# X_Axis_Stepper_Motor_Driver.net
KiCad netlist of a schematic drawn in Altium Designer
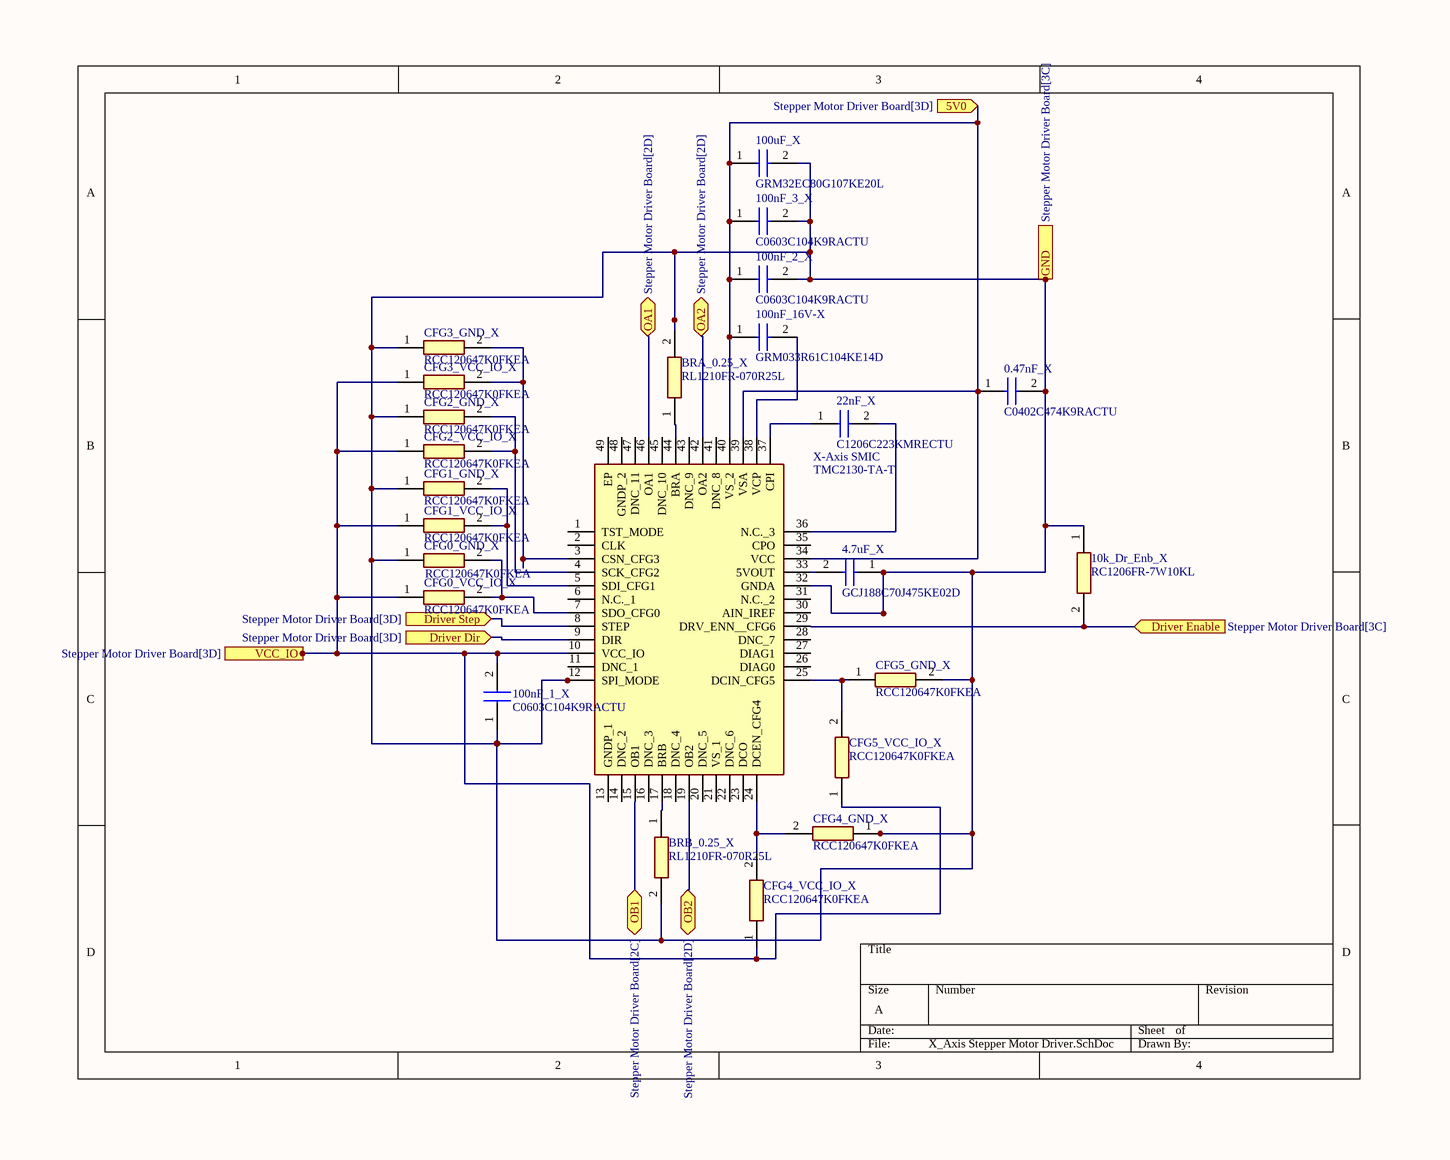
[diagram p0: X_Axis Stepper Motor Driver.SchDoc]

(export (version "E")
  (design (tool "Eeschema 10.0.6"))
  (components
    (comp (ref "0.47nF_X")
      (value "C0402C474K9RACTU")
      (footprint "SamacSys:CAPC1005X55N")
      (description "Capacitor")
      (fields (field (name "MOUSER PART NUMBER") "80-C0402C474K9RACTU"))
      (libsource (lib "*") (part "C0402C474K9RACTU"))
    )
    (comp (ref "4.7uF_X")
      (value "GCJ188C70J475KE02D")
      (footprint "SamacSys:CAPC1608X100N")
      (description "Capacitor")
      (fields (field (name "MOUSER PART NUMBER") "81-GCJ188C70J475KE2D"))
      (libsource (lib "*") (part "GCJ188C70J475KE02D"))
    )
    (comp (ref "10k_Dr_Enb_X")
      (value "RC1206FR-7W10KL")
      (footprint "SamacSys:RESC3116X65N")
      (description "Resistor")
      (libsource (lib "*") (part "RC1206FR-7W10KL"))
    )
    (comp (ref "22nF_X")
      (value "C1206C223KMRECTU")
      (footprint "SamacSys:C1206")
      (description "Capacitor")
      (fields (field (name "MOUSER PART NUMBER") "80-C1206C223KMRECTU"))
      (libsource (lib "*") (part "C1206C223KMRECTU"))
    )
    (comp (ref "100nF_1_X")
      (value "C0603C104K9RACTU")
      (footprint "SamacSys:C0603")
      (description "Capacitor")
      (fields (field (name "MOUSER PART NUMBER") "80-C0603C104K9R"))
      (libsource (lib "*") (part "C0603C104K9RACTU"))
    )
    (comp (ref "100nF_2_X")
      (value "C0603C104K9RACTU")
      (footprint "SamacSys:C0603")
      (description "Capacitor")
      (fields (field (name "MOUSER PART NUMBER") "80-C0603C104K9R"))
      (libsource (lib "*") (part "C0603C104K9RACTU"))
    )
    (comp (ref "100nF_3_X")
      (value "C0603C104K9RACTU")
      (footprint "SamacSys:C0603")
      (description "Capacitor")
      (fields (field (name "MOUSER PART NUMBER") "80-C0603C104K9R"))
      (libsource (lib "*") (part "C0603C104K9RACTU"))
    )
    (comp (ref "100nF_16V-X")
      (value "GRM033R61C104KE14D")
      (footprint "SamacSys:CAPC0603X33N")
      (description "Capacitor")
      (fields (field (name "MOUSER PART NUMBER") "81-GRM033R61C104KE4D"))
      (libsource (lib "*") (part "GRM033R61C104KE14D"))
    )
    (comp (ref "100uF_X")
      (value "GRM32EC80G107KE20L")
      (footprint "SamacSys:CAPC3225X270N")
      (description "Capacitor")
      (fields (field (name "MOUSER PART NUMBER") "81-GRM32EC80G107KE0L"))
      (libsource (lib "*") (part "GRM32EC80G107KE20L"))
    )
    (comp (ref "BRA_0.25_X")
      (value "RL1210FR-070R25L")
      (footprint "SamacSys:RESC3126X65N")
      (description "Resistor")
      (fields (field (name "MOUSER PART NUMBER") "603-RL1210FR-070R25L"))
      (libsource (lib "") (part "RL1210FR-070R25L_1"))
    )
    (comp (ref "BRB_0.25_X")
      (value "RL1210FR-070R25L")
      (footprint "SamacSys:RESC3126X65N")
      (description "Resistor")
      (fields (field (name "MOUSER PART NUMBER") "603-RL1210FR-070R25L"))
      (libsource (lib "*") (part "RL1210FR-070R25L"))
    )
    (comp (ref "CFG0_GND_X")
      (value "RCC120647K0FKEA")
      (footprint "SamacSys:RCC1206_e3")
      (description "Resistor")
      (fields (field (name "MOUSER PART NUMBER") "71-RCC120647K0FKEA"))
      (libsource (lib "") (part "RCC120647K0FKEA_1"))
    )
    (comp (ref "CFG0_VCC_IO_X")
      (value "RCC120647K0FKEA")
      (footprint "SamacSys:RCC1206_e3")
      (description "Resistor")
      (fields (field (name "MOUSER PART NUMBER") "71-RCC120647K0FKEA"))
      (libsource (lib "") (part "RCC120647K0FKEA_1"))
    )
    (comp (ref "CFG1_GND_X")
      (value "RCC120647K0FKEA")
      (footprint "SamacSys:RCC1206_e3")
      (description "Resistor")
      (fields (field (name "MOUSER PART NUMBER") "71-RCC120647K0FKEA"))
      (libsource (lib "") (part "RCC120647K0FKEA_1"))
    )
    (comp (ref "CFG1_VCC_IO_X")
      (value "RCC120647K0FKEA")
      (footprint "SamacSys:RCC1206_e3")
      (description "Resistor")
      (fields (field (name "MOUSER PART NUMBER") "71-RCC120647K0FKEA"))
      (libsource (lib "") (part "RCC120647K0FKEA_1"))
    )
    (comp (ref "CFG2_GND_X")
      (value "RCC120647K0FKEA")
      (footprint "SamacSys:RCC1206_e3")
      (description "Resistor")
      (fields (field (name "MOUSER PART NUMBER") "71-RCC120647K0FKEA"))
      (libsource (lib "") (part "RCC120647K0FKEA_1"))
    )
    (comp (ref "CFG2_VCC_IO_X")
      (value "RCC120647K0FKEA")
      (footprint "SamacSys:RCC1206_e3")
      (description "Resistor")
      (fields (field (name "MOUSER PART NUMBER") "71-RCC120647K0FKEA"))
      (libsource (lib "") (part "RCC120647K0FKEA_1"))
    )
    (comp (ref "CFG3_GND_X")
      (value "RCC120647K0FKEA")
      (footprint "SamacSys:RCC1206_e3")
      (description "Resistor")
      (fields (field (name "MOUSER PART NUMBER") "71-RCC120647K0FKEA"))
      (libsource (lib "") (part "RCC120647K0FKEA_1"))
    )
    (comp (ref "CFG3_VCC_IO_X")
      (value "RCC120647K0FKEA")
      (footprint "SamacSys:RCC1206_e3")
      (description "Resistor")
      (fields (field (name "MOUSER PART NUMBER") "71-RCC120647K0FKEA"))
      (libsource (lib "") (part "RCC120647K0FKEA_1"))
    )
    (comp (ref "CFG4_GND_X")
      (value "RCC120647K0FKEA")
      (footprint "SamacSys:RCC1206_e3")
      (description "Resistor")
      (fields (field (name "MOUSER PART NUMBER") "71-RCC120647K0FKEA"))
      (libsource (lib "") (part "RCC120647K0FKEA_2"))
    )
    (comp (ref "CFG4_VCC_IO_X")
      (value "RCC120647K0FKEA")
      (footprint "SamacSys:RCC1206_e3")
      (description "Resistor")
      (fields (field (name "MOUSER PART NUMBER") "71-RCC120647K0FKEA"))
      (libsource (lib "*") (part "RCC120647K0FKEA"))
    )
    (comp (ref "CFG5_GND_X")
      (value "RCC120647K0FKEA")
      (footprint "SamacSys:RCC1206_e3")
      (description "Resistor")
      (fields (field (name "MOUSER PART NUMBER") "71-RCC120647K0FKEA"))
      (libsource (lib "") (part "RCC120647K0FKEA_1"))
    )
    (comp (ref "CFG5_VCC_IO_X")
      (value "RCC120647K0FKEA")
      (footprint "SamacSys:RCC1206_e3")
      (description "Resistor")
      (fields (field (name "MOUSER PART NUMBER") "71-RCC120647K0FKEA"))
      (libsource (lib "*") (part "RCC120647K0FKEA"))
    )
    (comp (ref "X-Axis SMIC")
      (value "TMC2130-TA-T")
      (footprint "SamacSys:QFP50P900X900X120-49N")
      (description "Integrated Circuit")
      (fields (field (name "MOUSER PART NUMBER") "700-TMC2130-TA-T"))
      (libsource (lib "*") (part "TMC2130-TA-T"))
    )
  )
  (nets
    (net (code "1") (name "/5V0") (class "Default")
      (node (ref "0.47nF_X") (pin "1") (pinfunction "1_1") (pintype "passive"))
      (node (ref "100nF_16V-X") (pin "1") (pinfunction "1_1") (pintype "passive"))
      (node (ref "100nF_2_X") (pin "1") (pinfunction "1_1") (pintype "passive"))
      (node (ref "100nF_3_X") (pin "1") (pinfunction "1_1") (pintype "passive"))
      (node (ref "100uF_X") (pin "1") (pinfunction "1_1") (pintype "passive"))
      (node (ref "X-Axis SMIC") (pin "34") (pinfunction "VCC_34") (pintype "passive"))
      (node (ref "X-Axis SMIC") (pin "39") (pinfunction "VSA_39") (pintype "passive"))
      (node (ref "X-Axis SMIC") (pin "40") (pinfunction "VS_2_40") (pintype "passive"))
    )
    (net (code "2") (name "/Driver Dir") (class "Default")
      (node (ref "X-Axis SMIC") (pin "9") (pinfunction "DIR_9") (pintype "passive"))
    )
    (net (code "3") (name "/Driver Enable") (class "Default")
      (node (ref "10k_Dr_Enb_X") (pin "2") (pinfunction "2_2") (pintype "passive"))
      (node (ref "X-Axis SMIC") (pin "29") (pinfunction "DRV_ENN__CFG6_29") (pintype "passive"))
    )
    (net (code "4") (name "/Driver Step") (class "Default")
      (node (ref "X-Axis SMIC") (pin "8") (pinfunction "STEP_8") (pintype "passive"))
    )
    (net (code "5") (name "/GND") (class "Default")
      (node (ref "0.47nF_X") (pin "2") (pinfunction "2_2") (pintype "passive"))
      (node (ref "100nF_1_X") (pin "1") (pinfunction "1_1") (pintype "passive"))
      (node (ref "100nF_2_X") (pin "2") (pinfunction "2_2") (pintype "passive"))
      (node (ref "100nF_3_X") (pin "2") (pinfunction "2_2") (pintype "passive"))
      (node (ref "100uF_X") (pin "2") (pinfunction "2_2") (pintype "passive"))
      (node (ref "10k_Dr_Enb_X") (pin "1") (pinfunction "1_1") (pintype "passive"))
      (node (ref "4.7uF_X") (pin "1") (pinfunction "1_1") (pintype "passive"))
      (node (ref "BRA_0.25_X") (pin "2") (pinfunction "2_2") (pintype "passive"))
      (node (ref "BRB_0.25_X") (pin "2") (pinfunction "2_2") (pintype "passive"))
      (node (ref "CFG0_GND_X") (pin "1") (pinfunction "1_1") (pintype "passive"))
      (node (ref "CFG1_GND_X") (pin "1") (pinfunction "1_1") (pintype "passive"))
      (node (ref "CFG2_GND_X") (pin "1") (pinfunction "1_1") (pintype "passive"))
      (node (ref "CFG3_GND_X") (pin "1") (pinfunction "1_1") (pintype "passive"))
      (node (ref "CFG4_GND_X") (pin "1") (pinfunction "1_1") (pintype "passive"))
      (node (ref "CFG5_GND_X") (pin "2") (pinfunction "2_2") (pintype "passive"))
      (node (ref "X-Axis SMIC") (pin "12") (pinfunction "SPI_MODE_12") (pintype "passive"))
      (node (ref "X-Axis SMIC") (pin "32") (pinfunction "GNDA_32") (pintype "passive"))
    )
    (net (code "6") (name "/OA1") (class "Default")
      (node (ref "X-Axis SMIC") (pin "46") (pinfunction "OA1_46") (pintype "passive"))
    )
    (net (code "7") (name "/OA2") (class "Default")
      (node (ref "X-Axis SMIC") (pin "42") (pinfunction "OA2_42") (pintype "passive"))
    )
    (net (code "8") (name "/OB1") (class "Default")
      (node (ref "X-Axis SMIC") (pin "15") (pinfunction "OB1_15") (pintype "passive"))
    )
    (net (code "9") (name "/OB2") (class "Default")
      (node (ref "X-Axis SMIC") (pin "19") (pinfunction "OB2_19") (pintype "passive"))
    )
    (net (code "10") (name "/VCC_IO") (class "Default")
      (node (ref "100nF_1_X") (pin "2") (pinfunction "2_2") (pintype "passive"))
      (node (ref "CFG0_VCC_IO_X") (pin "1") (pinfunction "1_1") (pintype "passive"))
      (node (ref "CFG1_VCC_IO_X") (pin "1") (pinfunction "1_1") (pintype "passive"))
      (node (ref "CFG2_VCC_IO_X") (pin "1") (pinfunction "1_1") (pintype "passive"))
      (node (ref "CFG3_VCC_IO_X") (pin "1") (pinfunction "1_1") (pintype "passive"))
      (node (ref "CFG4_VCC_IO_X") (pin "1") (pinfunction "1_1") (pintype "passive"))
      (node (ref "CFG5_VCC_IO_X") (pin "1") (pinfunction "1_1") (pintype "passive"))
      (node (ref "X-Axis SMIC") (pin "10") (pinfunction "VCC_IO_10") (pintype "passive"))
    )
    (net (code "11") (name "Net-(X-Axis SMIC-5VOUT)") (class "Default")
      (node (ref "4.7uF_X") (pin "2") (pinfunction "2_2") (pintype "passive"))
      (node (ref "X-Axis SMIC") (pin "33") (pinfunction "5VOUT_33") (pintype "passive"))
    )
    (net (code "12") (name "Net-(X-Axis SMIC-BRA)") (class "Default")
      (node (ref "BRA_0.25_X") (pin "1") (pinfunction "1_1") (pintype "passive"))
      (node (ref "X-Axis SMIC") (pin "44") (pinfunction "BRA_44") (pintype "passive"))
    )
    (net (code "13") (name "Net-(X-Axis SMIC-BRB)") (class "Default")
      (node (ref "BRB_0.25_X") (pin "1") (pinfunction "1_1") (pintype "passive"))
      (node (ref "X-Axis SMIC") (pin "17") (pinfunction "BRB_17") (pintype "passive"))
    )
    (net (code "14") (name "Net-(X-Axis SMIC-CPI)") (class "Default")
      (node (ref "22nF_X") (pin "1") (pinfunction "1_1") (pintype "passive"))
      (node (ref "X-Axis SMIC") (pin "37") (pinfunction "CPI_37") (pintype "passive"))
    )
    (net (code "15") (name "Net-(X-Axis SMIC-CSN_CFG3)") (class "Default")
      (node (ref "CFG3_GND_X") (pin "2") (pinfunction "2_2") (pintype "passive"))
      (node (ref "CFG3_VCC_IO_X") (pin "2") (pinfunction "2_2") (pintype "passive"))
      (node (ref "X-Axis SMIC") (pin "3") (pinfunction "CSN_CFG3_3") (pintype "passive"))
    )
    (net (code "16") (name "Net-(X-Axis SMIC-DCEN_CFG4)") (class "Default")
      (node (ref "CFG4_GND_X") (pin "2") (pinfunction "2_2") (pintype "passive"))
      (node (ref "CFG4_VCC_IO_X") (pin "2") (pinfunction "2_2") (pintype "passive"))
      (node (ref "X-Axis SMIC") (pin "24") (pinfunction "DCEN_CFG4_24") (pintype "passive"))
    )
    (net (code "17") (name "Net-(X-Axis SMIC-DCIN_CFG5)") (class "Default")
      (node (ref "CFG5_GND_X") (pin "1") (pinfunction "1_1") (pintype "passive"))
      (node (ref "CFG5_VCC_IO_X") (pin "2") (pinfunction "2_2") (pintype "passive"))
      (node (ref "X-Axis SMIC") (pin "25") (pinfunction "DCIN_CFG5_25") (pintype "passive"))
    )
    (net (code "18") (name "Net-(X-Axis SMIC-N.C._3)") (class "Default")
      (node (ref "22nF_X") (pin "2") (pinfunction "2_2") (pintype "passive"))
      (node (ref "X-Axis SMIC") (pin "36") (pinfunction "N.C._3_36") (pintype "passive"))
    )
    (net (code "19") (name "Net-(X-Axis SMIC-SCK_CFG2)") (class "Default")
      (node (ref "CFG2_GND_X") (pin "2") (pinfunction "2_2") (pintype "passive"))
      (node (ref "CFG2_VCC_IO_X") (pin "2") (pinfunction "2_2") (pintype "passive"))
      (node (ref "X-Axis SMIC") (pin "4") (pinfunction "SCK_CFG2_4") (pintype "passive"))
    )
    (net (code "20") (name "Net-(X-Axis SMIC-SDI_CFG1)") (class "Default")
      (node (ref "CFG1_GND_X") (pin "2") (pinfunction "2_2") (pintype "passive"))
      (node (ref "CFG1_VCC_IO_X") (pin "2") (pinfunction "2_2") (pintype "passive"))
      (node (ref "X-Axis SMIC") (pin "5") (pinfunction "SDI_CFG1_5") (pintype "passive"))
    )
    (net (code "21") (name "Net-(X-Axis SMIC-SDO_CFG0)") (class "Default")
      (node (ref "CFG0_GND_X") (pin "2") (pinfunction "2_2") (pintype "passive"))
      (node (ref "CFG0_VCC_IO_X") (pin "2") (pinfunction "2_2") (pintype "passive"))
      (node (ref "X-Axis SMIC") (pin "7") (pinfunction "SDO_CFG0_7") (pintype "passive"))
    )
    (net (code "22") (name "Net-(X-Axis SMIC-VCP)") (class "Default")
      (node (ref "100nF_16V-X") (pin "2") (pinfunction "2_2") (pintype "passive"))
      (node (ref "X-Axis SMIC") (pin "38") (pinfunction "VCP_38") (pintype "passive"))
    )
    (net (code "23") (name "unconnected-(X-Axis SMIC-AIN_IREF-Pad30)") (class "Default")
      (node (ref "X-Axis SMIC") (pin "30") (pinfunction "AIN_IREF_30") (pintype "passive"))
    )
    (net (code "24") (name "unconnected-(X-Axis SMIC-CLK-Pad2)") (class "Default")
      (node (ref "X-Axis SMIC") (pin "2") (pinfunction "CLK_2") (pintype "passive"))
    )
    (net (code "25") (name "unconnected-(X-Axis SMIC-CPO-Pad35)") (class "Default")
      (node (ref "X-Axis SMIC") (pin "35") (pinfunction "CPO_35") (pintype "passive"))
    )
    (net (code "26") (name "unconnected-(X-Axis SMIC-DCO-Pad23)") (class "Default")
      (node (ref "X-Axis SMIC") (pin "23") (pinfunction "DCO_23") (pintype "passive"))
    )
    (net (code "27") (name "unconnected-(X-Axis SMIC-DIAG0-Pad26)") (class "Default")
      (node (ref "X-Axis SMIC") (pin "26") (pinfunction "DIAG0_26") (pintype "passive"))
    )
    (net (code "28") (name "unconnected-(X-Axis SMIC-DIAG1-Pad27)") (class "Default")
      (node (ref "X-Axis SMIC") (pin "27") (pinfunction "DIAG1_27") (pintype "passive"))
    )
    (net (code "29") (name "unconnected-(X-Axis SMIC-DNC_1-Pad11)") (class "Default")
      (node (ref "X-Axis SMIC") (pin "11") (pinfunction "DNC_1_11") (pintype "passive"))
    )
    (net (code "30") (name "unconnected-(X-Axis SMIC-DNC_2-Pad14)") (class "Default")
      (node (ref "X-Axis SMIC") (pin "14") (pinfunction "DNC_2_14") (pintype "passive"))
    )
    (net (code "31") (name "unconnected-(X-Axis SMIC-DNC_3-Pad16)") (class "Default")
      (node (ref "X-Axis SMIC") (pin "16") (pinfunction "DNC_3_16") (pintype "passive"))
    )
    (net (code "32") (name "unconnected-(X-Axis SMIC-DNC_4-Pad18)") (class "Default")
      (node (ref "X-Axis SMIC") (pin "18") (pinfunction "DNC_4_18") (pintype "passive"))
    )
    (net (code "33") (name "unconnected-(X-Axis SMIC-DNC_5-Pad20)") (class "Default")
      (node (ref "X-Axis SMIC") (pin "20") (pinfunction "DNC_5_20") (pintype "passive"))
    )
    (net (code "34") (name "unconnected-(X-Axis SMIC-DNC_6-Pad22)") (class "Default")
      (node (ref "X-Axis SMIC") (pin "22") (pinfunction "DNC_6_22") (pintype "passive"))
    )
    (net (code "35") (name "unconnected-(X-Axis SMIC-DNC_7-Pad28)") (class "Default")
      (node (ref "X-Axis SMIC") (pin "28") (pinfunction "DNC_7_28") (pintype "passive"))
    )
    (net (code "36") (name "unconnected-(X-Axis SMIC-DNC_8-Pad41)") (class "Default")
      (node (ref "X-Axis SMIC") (pin "41") (pinfunction "DNC_8_41") (pintype "passive"))
    )
    (net (code "37") (name "unconnected-(X-Axis SMIC-DNC_9-Pad43)") (class "Default")
      (node (ref "X-Axis SMIC") (pin "43") (pinfunction "DNC_9_43") (pintype "passive"))
    )
    (net (code "38") (name "unconnected-(X-Axis SMIC-DNC_10-Pad45)") (class "Default")
      (node (ref "X-Axis SMIC") (pin "45") (pinfunction "DNC_10_45") (pintype "passive"))
    )
    (net (code "39") (name "unconnected-(X-Axis SMIC-DNC_11-Pad47)") (class "Default")
      (node (ref "X-Axis SMIC") (pin "47") (pinfunction "DNC_11_47") (pintype "passive"))
    )
    (net (code "40") (name "unconnected-(X-Axis SMIC-EP-Pad49)") (class "Default")
      (node (ref "X-Axis SMIC") (pin "49") (pinfunction "EP_49") (pintype "passive"))
    )
    (net (code "41") (name "unconnected-(X-Axis SMIC-GNDP_1-Pad13)") (class "Default")
      (node (ref "X-Axis SMIC") (pin "13") (pinfunction "GNDP_1_13") (pintype "passive"))
    )
    (net (code "42") (name "unconnected-(X-Axis SMIC-GNDP_2-Pad48)") (class "Default")
      (node (ref "X-Axis SMIC") (pin "48") (pinfunction "GNDP_2_48") (pintype "passive"))
    )
    (net (code "43") (name "unconnected-(X-Axis SMIC-N.C._1-Pad6)") (class "Default")
      (node (ref "X-Axis SMIC") (pin "6") (pinfunction "N.C._1_6") (pintype "passive"))
    )
    (net (code "44") (name "unconnected-(X-Axis SMIC-N.C._2-Pad31)") (class "Default")
      (node (ref "X-Axis SMIC") (pin "31") (pinfunction "N.C._2_31") (pintype "passive"))
    )
    (net (code "45") (name "unconnected-(X-Axis SMIC-TST_MODE-Pad1)") (class "Default")
      (node (ref "X-Axis SMIC") (pin "1") (pinfunction "TST_MODE_1") (pintype "passive"))
    )
    (net (code "46") (name "unconnected-(X-Axis SMIC-VS_1-Pad21)") (class "Default")
      (node (ref "X-Axis SMIC") (pin "21") (pinfunction "VS_1_21") (pintype "passive"))
    )
  )
)
